# Simple_RC.net
KiCad netlist of a schematic drawn in Altium Designer
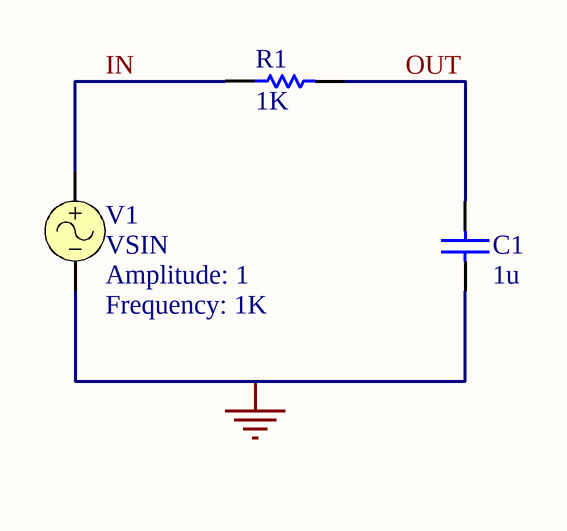
[diagram p0: Simple RC.SchDoc]

(export (version "E")
  (design (tool "Eeschema 10.0.6"))
  (components
    (comp (ref "C1")
      (value "1u")
      (footprint "RAD-0.3")
      (description "Capacitor")
      (fields
        (field (name "MANUFACTURER") "Generic Components")
        (field (name "Comment") "Cap")
        (field (name "PUBLISHER") "Altium Limited")
      )
      (libsource (lib "Miscellaneous Devices") (part "Cap"))
    )
    (comp (ref "R1")
      (value "1K")
      (footprint "AXIAL-0.3")
      (description "Resistor")
      (fields
        (field (name "MANUFACTURER") "Generic Components")
        (field (name "Comment") "Res1")
        (field (name "PUBLISHER") "Altium Limited")
      )
      (libsource (lib "Miscellaneous Devices") (part "Res1"))
    )
    (comp (ref "V1")
      (value "VSIN")
      (description "Sinusoidal Voltage Source")
      (fields
        (field (name "MANUFACTURER") "Generic Components")
        (field (name "AMPLITUDE") "1")
        (field (name "FREQUENCY") "1K")
        (field (name "PUBLISHER") "Altium Limited")
      )
      (libsource (lib "Simulation Sources") (part "VSIN"))
    )
  )
  (nets
    (net (code "1") (name "/IN") (class "Default")
      (node (ref "R1") (pin "1") (pinfunction "1_1") (pintype "passive"))
      (node (ref "V1") (pin "1") (pinfunction "1_1") (pintype "passive"))
    )
    (net (code "2") (name "/OUT") (class "Default")
      (node (ref "C1") (pin "2") (pinfunction "2_2") (pintype "passive"))
      (node (ref "R1") (pin "2") (pinfunction "2_2") (pintype "passive"))
    )
    (net (code "4") (name "GND") (class "Default")
      (node (ref "C1") (pin "1") (pinfunction "1_1") (pintype "passive"))
      (node (ref "V1") (pin "2") (pinfunction "2_2") (pintype "passive"))
    )
  )
)
